# Clock_fanout.net
KiCad netlist of a schematic drawn in Altium Designer
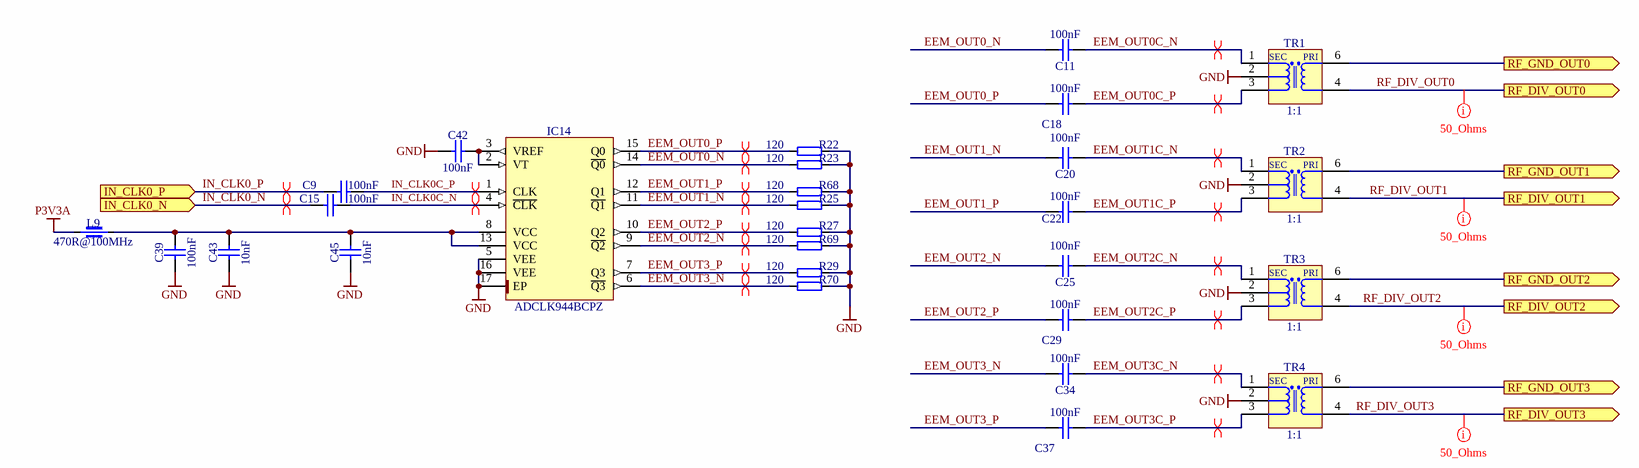
[diagram p0: Clock_fanout.SchDoc]

(export (version "E")
  (design (tool "Eeschema 10.0.6"))
  (components
    (comp (ref "C9")
      (value "100nF")
      (footprint "CAPC1005X55N")
      (description "Non-polarised capacitor")
      (fields
        (field (name "PART NUMBER") "CC0402_100NF_16V_10%_X5R")
        (field (name "VOLTAGE") "16V")
        (field (name "AUTHOR") "CERN DEM JLC")
      )
      (libsource (lib "Capacitors") (part "Capacitor - non polarized"))
    )
    (comp (ref "C11")
      (value "100nF")
      (footprint "CAPC1005X55N")
      (description "Non-polarised capacitor")
      (fields
        (field (name "PART NUMBER") "CC0402_100NF_16V_10%_X5R")
        (field (name "VOLTAGE") "16V")
        (field (name "AUTHOR") "CERN DEM JLC")
      )
      (libsource (lib "Capacitors") (part "Capacitor - non polarized"))
    )
    (comp (ref "C15")
      (value "100nF")
      (footprint "CAPC1005X55N")
      (description "Non-polarised capacitor")
      (fields
        (field (name "PART NUMBER") "CC0402_100NF_16V_10%_X5R")
        (field (name "VOLTAGE") "16V")
        (field (name "AUTHOR") "CERN DEM JLC")
      )
      (libsource (lib "Capacitors") (part "Capacitor - non polarized"))
    )
    (comp (ref "C18")
      (value "100nF")
      (footprint "CAPC1005X55N")
      (description "Non-polarised capacitor")
      (fields
        (field (name "PART NUMBER") "CC0402_100NF_16V_10%_X5R")
        (field (name "VOLTAGE") "16V")
        (field (name "AUTHOR") "CERN DEM JLC")
      )
      (libsource (lib "Capacitors") (part "Capacitor - non polarized"))
    )
    (comp (ref "C20")
      (value "100nF")
      (footprint "CAPC1005X55N")
      (description "Non-polarised capacitor")
      (fields
        (field (name "PART NUMBER") "CC0402_100NF_16V_10%_X5R")
        (field (name "VOLTAGE") "16V")
        (field (name "AUTHOR") "CERN DEM JLC")
      )
      (libsource (lib "Capacitors") (part "Capacitor - non polarized"))
    )
    (comp (ref "C22")
      (value "100nF")
      (footprint "CAPC1005X55N")
      (description "Non-polarised capacitor")
      (fields
        (field (name "PART NUMBER") "CC0402_100NF_16V_10%_X5R")
        (field (name "VOLTAGE") "16V")
        (field (name "AUTHOR") "CERN DEM JLC")
      )
      (libsource (lib "Capacitors") (part "Capacitor - non polarized"))
    )
    (comp (ref "C25")
      (value "100nF")
      (footprint "CAPC1005X55N")
      (description "Non-polarised capacitor")
      (fields
        (field (name "PART NUMBER") "CC0402_100NF_16V_10%_X5R")
        (field (name "VOLTAGE") "16V")
        (field (name "AUTHOR") "CERN DEM JLC")
      )
      (libsource (lib "Capacitors") (part "Capacitor - non polarized"))
    )
    (comp (ref "C29")
      (value "100nF")
      (footprint "CAPC1005X55N")
      (description "Non-polarised capacitor")
      (fields
        (field (name "PART NUMBER") "CC0402_100NF_16V_10%_X5R")
        (field (name "VOLTAGE") "16V")
        (field (name "AUTHOR") "CERN DEM JLC")
      )
      (libsource (lib "Capacitors") (part "Capacitor - non polarized"))
    )
    (comp (ref "C34")
      (value "100nF")
      (footprint "CAPC1005X55N")
      (description "Non-polarised capacitor")
      (fields
        (field (name "PART NUMBER") "CC0402_100NF_16V_10%_X5R")
        (field (name "VOLTAGE") "16V")
        (field (name "AUTHOR") "CERN DEM JLC")
      )
      (libsource (lib "Capacitors") (part "Capacitor - non polarized"))
    )
    (comp (ref "C37")
      (value "100nF")
      (footprint "CAPC1005X55N")
      (description "Non-polarised capacitor")
      (fields
        (field (name "PART NUMBER") "CC0402_100NF_16V_10%_X5R")
        (field (name "VOLTAGE") "16V")
        (field (name "AUTHOR") "CERN DEM JLC")
      )
      (libsource (lib "Capacitors") (part "Capacitor - non polarized"))
    )
    (comp (ref "C39")
      (value "100nF")
      (footprint "CAPC1005X55N")
      (description "Non-polarised capacitor")
      (fields
        (field (name "PART NUMBER") "CC0402_100NF_16V_10%_X5R")
        (field (name "VOLTAGE") "16V")
        (field (name "AUTHOR") "CERN DEM JLC")
      )
      (libsource (lib "Capacitors") (part "Capacitor - non polarized"))
    )
    (comp (ref "C42")
      (value "100nF")
      (footprint "CAPC1005X55N")
      (description "Non-polarised capacitor")
      (fields
        (field (name "PART NUMBER") "CC0402_100NF_16V_10%_X5R")
        (field (name "VOLTAGE") "16V")
        (field (name "AUTHOR") "CERN DEM JLC")
      )
      (libsource (lib "Capacitors") (part "Capacitor - non polarized"))
    )
    (comp (ref "C43")
      (value "10nF")
      (footprint "CAPC1005X55N")
      (description "Non-polarised capacitor")
      (fields
        (field (name "PART NUMBER") "CC0402_10NF_16V_10%_X7R")
        (field (name "VOLTAGE") "16V")
        (field (name "AUTHOR") "CERN DEM JLC")
      )
      (libsource (lib "Capacitors") (part "Capacitor - non polarized"))
    )
    (comp (ref "C45")
      (value "10nF")
      (footprint "CAPC1005X55N")
      (description "Non-polarised capacitor")
      (fields
        (field (name "PART NUMBER") "CC0402_10NF_16V_10%_X7R")
        (field (name "VOLTAGE") "16V")
        (field (name "AUTHOR") "CERN DEM JLC")
      )
      (libsource (lib "Capacitors") (part "Capacitor - non polarized"))
    )
    (comp (ref "IC14")
      (value "ADCLK944BCPZ")
      (footprint "QFN50P300X300X80-17N-S160")
      (description "2.5V/3.3V, Four LVPECL Outputs, SiGe Clock Fanout Buffer")
      (fields
        (field (name "MANUFACTURER") "ANALOG DEVICES")
        (field (name "MANUFACTURER PART NUMBER") "ADCLK944BCP")
        (field (name "AUTHOR") "CERN DEM JLC")
      )
      (libsource (lib "ICs And Semiconductors") (part "ADCLK944"))
    )
    (comp (ref "L9")
      (value "470R@100MHz")
      (footprint "INDC1608X95N")
      (fields
        (field (name "PART NUMBER") "IND0603_MURATA_BLM18PG471SN1D")
        (field (name "POWER") "1A")
        (field (name "TOLERANCE") "±25%")
        (field (name "AUTHOR") "CERN DEM BC")
      )
      (libsource (lib "Inductors & Transformers") (part "Ferrite Bead"))
    )
    (comp (ref "R22")
      (value "120")
      (footprint "RESC1005X40N")
      (description "Resistor - 1%")
      (fields
        (field (name "PART NUMBER") "R0402_120R_1%_0.0625W_100PPM")
        (field (name "POWER") "0.0625W")
        (field (name "AUTHOR") "CERN DEM JLC")
      )
      (libsource (lib "Resistors") (part "Resistor - 1%"))
    )
    (comp (ref "R23")
      (value "120")
      (footprint "RESC1005X40N")
      (description "Resistor - 1%")
      (fields
        (field (name "PART NUMBER") "R0402_120R_1%_0.0625W_100PPM")
        (field (name "POWER") "0.0625W")
        (field (name "AUTHOR") "CERN DEM JLC")
      )
      (libsource (lib "Resistors") (part "Resistor - 1%"))
    )
    (comp (ref "R25")
      (value "120")
      (footprint "RESC1005X40N")
      (description "Resistor - 1%")
      (fields
        (field (name "PART NUMBER") "R0402_120R_1%_0.0625W_100PPM")
        (field (name "POWER") "0.0625W")
        (field (name "AUTHOR") "CERN DEM JLC")
      )
      (libsource (lib "Resistors") (part "Resistor - 1%"))
    )
    (comp (ref "R27")
      (value "120")
      (footprint "RESC1005X40N")
      (description "Resistor - 1%")
      (fields
        (field (name "PART NUMBER") "R0402_120R_1%_0.0625W_100PPM")
        (field (name "POWER") "0.0625W")
        (field (name "AUTHOR") "CERN DEM JLC")
      )
      (libsource (lib "Resistors") (part "Resistor - 1%"))
    )
    (comp (ref "R29")
      (value "120")
      (footprint "RESC1005X40N")
      (description "Resistor - 1%")
      (fields
        (field (name "PART NUMBER") "R0402_120R_1%_0.0625W_100PPM")
        (field (name "POWER") "0.0625W")
        (field (name "AUTHOR") "CERN DEM JLC")
      )
      (libsource (lib "Resistors") (part "Resistor - 1%"))
    )
    (comp (ref "R68")
      (value "120")
      (footprint "RESC1005X40N")
      (description "Resistor - 1%")
      (fields
        (field (name "PART NUMBER") "R0402_120R_1%_0.0625W_100PPM")
        (field (name "POWER") "0.0625W")
        (field (name "AUTHOR") "CERN DEM JLC")
      )
      (libsource (lib "Resistors") (part "Resistor - 1%"))
    )
    (comp (ref "R69")
      (value "120")
      (footprint "RESC1005X40N")
      (description "Resistor - 1%")
      (fields
        (field (name "PART NUMBER") "R0402_120R_1%_0.0625W_100PPM")
        (field (name "POWER") "0.0625W")
        (field (name "AUTHOR") "CERN DEM JLC")
      )
      (libsource (lib "Resistors") (part "Resistor - 1%"))
    )
    (comp (ref "R70")
      (value "120")
      (footprint "RESC1005X40N")
      (description "Resistor - 1%")
      (fields
        (field (name "PART NUMBER") "R0402_120R_1%_0.0625W_100PPM")
        (field (name "POWER") "0.0625W")
        (field (name "AUTHOR") "CERN DEM JLC")
      )
      (libsource (lib "Resistors") (part "Resistor - 1%"))
    )
    (comp (ref "TR1")
      (value "1:1")
      (footprint "XFMR_MINI-CIRCUITS_AT1521")
      (description "50 Ohms 3 to 300MHz RF Transformer")
      (fields
        (field (name "PART NUMBER") "XFMR_MINI-CIRCUITS_TC2-1TX+")
        (field (name "MANUFACTURER") "MINI-CIRCUITS")
        (field (name "AUTHOR") "CERN DEM MR")
      )
      (libsource (lib "Inductors & Transformers") (part "XFMR_MINI-CIRCUITS_TC2-1TX+"))
    )
    (comp (ref "TR2")
      (value "1:1")
      (footprint "XFMR_MINI-CIRCUITS_AT1521")
      (description "50 Ohms 3 to 300MHz RF Transformer")
      (fields
        (field (name "PART NUMBER") "XFMR_MINI-CIRCUITS_TC2-1TX+")
        (field (name "MANUFACTURER") "MINI-CIRCUITS")
        (field (name "AUTHOR") "CERN DEM MR")
      )
      (libsource (lib "Inductors & Transformers") (part "XFMR_MINI-CIRCUITS_TC2-1TX+"))
    )
    (comp (ref "TR3")
      (value "1:1")
      (footprint "XFMR_MINI-CIRCUITS_AT1521")
      (description "50 Ohms 3 to 300MHz RF Transformer")
      (fields
        (field (name "PART NUMBER") "XFMR_MINI-CIRCUITS_TC2-1TX+")
        (field (name "MANUFACTURER") "MINI-CIRCUITS")
        (field (name "AUTHOR") "CERN DEM MR")
      )
      (libsource (lib "Inductors & Transformers") (part "XFMR_MINI-CIRCUITS_TC2-1TX+"))
    )
    (comp (ref "TR4")
      (value "1:1")
      (footprint "XFMR_MINI-CIRCUITS_AT1521")
      (description "50 Ohms 3 to 300MHz RF Transformer")
      (fields
        (field (name "PART NUMBER") "XFMR_MINI-CIRCUITS_TC2-1TX+")
        (field (name "MANUFACTURER") "MINI-CIRCUITS")
        (field (name "AUTHOR") "CERN DEM MR")
      )
      (libsource (lib "Inductors & Transformers") (part "XFMR_MINI-CIRCUITS_TC2-1TX+"))
    )
  )
  (nets
    (net (code "1") (name "/EEM_OUT0C_N") (class "Default")
      (node (ref "C11") (pin "1") (pinfunction "1_1") (pintype "passive"))
      (node (ref "TR1") (pin "1") (pinfunction "SDOT_1") (pintype "passive"))
    )
    (net (code "2") (name "/EEM_OUT0C_P") (class "Default")
      (node (ref "C18") (pin "1") (pinfunction "1_1") (pintype "passive"))
      (node (ref "TR1") (pin "3") (pinfunction "S_3") (pintype "passive"))
    )
    (net (code "3") (name "/EEM_OUT0_N") (class "Default")
      (node (ref "C11") (pin "2") (pinfunction "2_2") (pintype "passive"))
      (node (ref "IC14") (pin "14") (pinfunction "~{Q0}_14") (pintype "output"))
      (node (ref "R23") (pin "1") (pinfunction "1_1") (pintype "passive"))
    )
    (net (code "4") (name "/EEM_OUT0_P") (class "Default")
      (node (ref "C18") (pin "2") (pinfunction "2_2") (pintype "passive"))
      (node (ref "IC14") (pin "15") (pinfunction "Q0_15") (pintype "output"))
      (node (ref "R22") (pin "1") (pinfunction "1_1") (pintype "passive"))
    )
    (net (code "5") (name "/EEM_OUT1C_N") (class "Default")
      (node (ref "C20") (pin "1") (pinfunction "1_1") (pintype "passive"))
      (node (ref "TR2") (pin "1") (pinfunction "SDOT_1") (pintype "passive"))
    )
    (net (code "6") (name "/EEM_OUT1C_P") (class "Default")
      (node (ref "C22") (pin "1") (pinfunction "1_1") (pintype "passive"))
      (node (ref "TR2") (pin "3") (pinfunction "S_3") (pintype "passive"))
    )
    (net (code "7") (name "/EEM_OUT1_N") (class "Default")
      (node (ref "C20") (pin "2") (pinfunction "2_2") (pintype "passive"))
      (node (ref "IC14") (pin "11") (pinfunction "~{Q1}_11") (pintype "output"))
      (node (ref "R25") (pin "1") (pinfunction "1_1") (pintype "passive"))
    )
    (net (code "8") (name "/EEM_OUT1_P") (class "Default")
      (node (ref "C22") (pin "2") (pinfunction "2_2") (pintype "passive"))
      (node (ref "IC14") (pin "12") (pinfunction "Q1_12") (pintype "output"))
      (node (ref "R68") (pin "1") (pinfunction "1_1") (pintype "passive"))
    )
    (net (code "9") (name "/EEM_OUT2C_N") (class "Default")
      (node (ref "C25") (pin "1") (pinfunction "1_1") (pintype "passive"))
      (node (ref "TR3") (pin "1") (pinfunction "SDOT_1") (pintype "passive"))
    )
    (net (code "10") (name "/EEM_OUT2C_P") (class "Default")
      (node (ref "C29") (pin "1") (pinfunction "1_1") (pintype "passive"))
      (node (ref "TR3") (pin "3") (pinfunction "S_3") (pintype "passive"))
    )
    (net (code "11") (name "/EEM_OUT2_N") (class "Default")
      (node (ref "C25") (pin "2") (pinfunction "2_2") (pintype "passive"))
      (node (ref "IC14") (pin "9") (pinfunction "~{Q2}_9") (pintype "output"))
      (node (ref "R69") (pin "1") (pinfunction "1_1") (pintype "passive"))
    )
    (net (code "12") (name "/EEM_OUT2_P") (class "Default")
      (node (ref "C29") (pin "2") (pinfunction "2_2") (pintype "passive"))
      (node (ref "IC14") (pin "10") (pinfunction "Q2_10") (pintype "output"))
      (node (ref "R27") (pin "1") (pinfunction "1_1") (pintype "passive"))
    )
    (net (code "13") (name "/EEM_OUT3C_N") (class "Default")
      (node (ref "C34") (pin "1") (pinfunction "1_1") (pintype "passive"))
      (node (ref "TR4") (pin "1") (pinfunction "SDOT_1") (pintype "passive"))
    )
    (net (code "14") (name "/EEM_OUT3C_P") (class "Default")
      (node (ref "C37") (pin "1") (pinfunction "1_1") (pintype "passive"))
      (node (ref "TR4") (pin "3") (pinfunction "S_3") (pintype "passive"))
    )
    (net (code "15") (name "/EEM_OUT3_N") (class "Default")
      (node (ref "C34") (pin "2") (pinfunction "2_2") (pintype "passive"))
      (node (ref "IC14") (pin "6") (pinfunction "~{Q3}_6") (pintype "output"))
      (node (ref "R70") (pin "1") (pinfunction "1_1") (pintype "passive"))
    )
    (net (code "16") (name "/EEM_OUT3_P") (class "Default")
      (node (ref "C37") (pin "2") (pinfunction "2_2") (pintype "passive"))
      (node (ref "IC14") (pin "7") (pinfunction "Q3_7") (pintype "output"))
      (node (ref "R29") (pin "1") (pinfunction "1_1") (pintype "passive"))
    )
    (net (code "17") (name "/IN_CLK0C_N") (class "Default")
      (node (ref "C15") (pin "2") (pinfunction "2_2") (pintype "passive"))
      (node (ref "IC14") (pin "4") (pinfunction "~{CLK}_4") (pintype "input"))
    )
    (net (code "18") (name "/IN_CLK0C_P") (class "Default")
      (node (ref "C9") (pin "2") (pinfunction "2_2") (pintype "passive"))
      (node (ref "IC14") (pin "1") (pinfunction "CLK_1") (pintype "input"))
    )
    (net (code "19") (name "/IN_CLK0_N") (class "Default")
      (node (ref "C15") (pin "1") (pinfunction "1_1") (pintype "passive"))
    )
    (net (code "20") (name "/IN_CLK0_P") (class "Default")
      (node (ref "C9") (pin "1") (pinfunction "1_1") (pintype "passive"))
    )
    (net (code "21") (name "/RF_DIV_OUT0") (class "Default")
      (node (ref "TR1") (pin "4") (pinfunction "P_4") (pintype "passive"))
    )
    (net (code "22") (name "/RF_DIV_OUT1") (class "Default")
      (node (ref "TR2") (pin "4") (pinfunction "P_4") (pintype "passive"))
    )
    (net (code "23") (name "/RF_DIV_OUT2") (class "Default")
      (node (ref "TR3") (pin "4") (pinfunction "P_4") (pintype "passive"))
    )
    (net (code "24") (name "/RF_DIV_OUT3") (class "Default")
      (node (ref "TR4") (pin "4") (pinfunction "P_4") (pintype "passive"))
    )
    (net (code "25") (name "/RF_GND_OUT0") (class "Default")
      (node (ref "TR1") (pin "6") (pinfunction "PDOT_6") (pintype "passive"))
    )
    (net (code "26") (name "/RF_GND_OUT1") (class "Default")
      (node (ref "TR2") (pin "6") (pinfunction "PDOT_6") (pintype "passive"))
    )
    (net (code "27") (name "/RF_GND_OUT2") (class "Default")
      (node (ref "TR3") (pin "6") (pinfunction "PDOT_6") (pintype "passive"))
    )
    (net (code "28") (name "/RF_GND_OUT3") (class "Default")
      (node (ref "TR4") (pin "6") (pinfunction "PDOT_6") (pintype "passive"))
    )
    (net (code "29") (name "GND") (class "Default")
      (node (ref "C39") (pin "1") (pinfunction "1_1") (pintype "passive"))
      (node (ref "C42") (pin "1") (pinfunction "1_1") (pintype "passive"))
      (node (ref "C43") (pin "1") (pinfunction "1_1") (pintype "passive"))
      (node (ref "C45") (pin "1") (pinfunction "1_1") (pintype "passive"))
      (node (ref "IC14") (pin "16") (pinfunction "VEE_16") (pintype "power_in"))
      (node (ref "IC14") (pin "17") (pinfunction "EP_17") (pintype "power_in"))
      (node (ref "IC14") (pin "5") (pinfunction "VEE_5") (pintype "power_in"))
      (node (ref "R22") (pin "2") (pinfunction "2_2") (pintype "passive"))
      (node (ref "R23") (pin "2") (pinfunction "2_2") (pintype "passive"))
      (node (ref "R25") (pin "2") (pinfunction "2_2") (pintype "passive"))
      (node (ref "R27") (pin "2") (pinfunction "2_2") (pintype "passive"))
      (node (ref "R29") (pin "2") (pinfunction "2_2") (pintype "passive"))
      (node (ref "R68") (pin "2") (pinfunction "2_2") (pintype "passive"))
      (node (ref "R69") (pin "2") (pinfunction "2_2") (pintype "passive"))
      (node (ref "R70") (pin "2") (pinfunction "2_2") (pintype "passive"))
      (node (ref "TR1") (pin "2") (pinfunction "NC_2") (pintype "passive"))
      (node (ref "TR2") (pin "2") (pinfunction "NC_2") (pintype "passive"))
      (node (ref "TR3") (pin "2") (pinfunction "NC_2") (pintype "passive"))
      (node (ref "TR4") (pin "2") (pinfunction "NC_2") (pintype "passive"))
    )
    (net (code "30") (name "Net-(C39-Pad2)") (class "Default")
      (node (ref "C39") (pin "2") (pinfunction "2_2") (pintype "passive"))
      (node (ref "C43") (pin "2") (pinfunction "2_2") (pintype "passive"))
      (node (ref "C45") (pin "2") (pinfunction "2_2") (pintype "passive"))
      (node (ref "IC14") (pin "13") (pinfunction "VCC_13") (pintype "power_in"))
      (node (ref "IC14") (pin "8") (pinfunction "VCC_8") (pintype "power_in"))
      (node (ref "L9") (pin "2") (pinfunction "2_2") (pintype "passive"))
    )
    (net (code "31") (name "Net-(IC14-VREF)") (class "Default")
      (node (ref "C42") (pin "2") (pinfunction "2_2") (pintype "passive"))
      (node (ref "IC14") (pin "2") (pinfunction "VT_2") (pintype "input"))
      (node (ref "IC14") (pin "3") (pinfunction "VREF_3") (pintype "output"))
    )
    (net (code "32") (name "P3V3A") (class "Default")
      (node (ref "L9") (pin "1") (pinfunction "1_1") (pintype "passive"))
    )
  )
)
